# ARM_Motor.net
KiCad netlist of a schematic drawn in Altium Designer
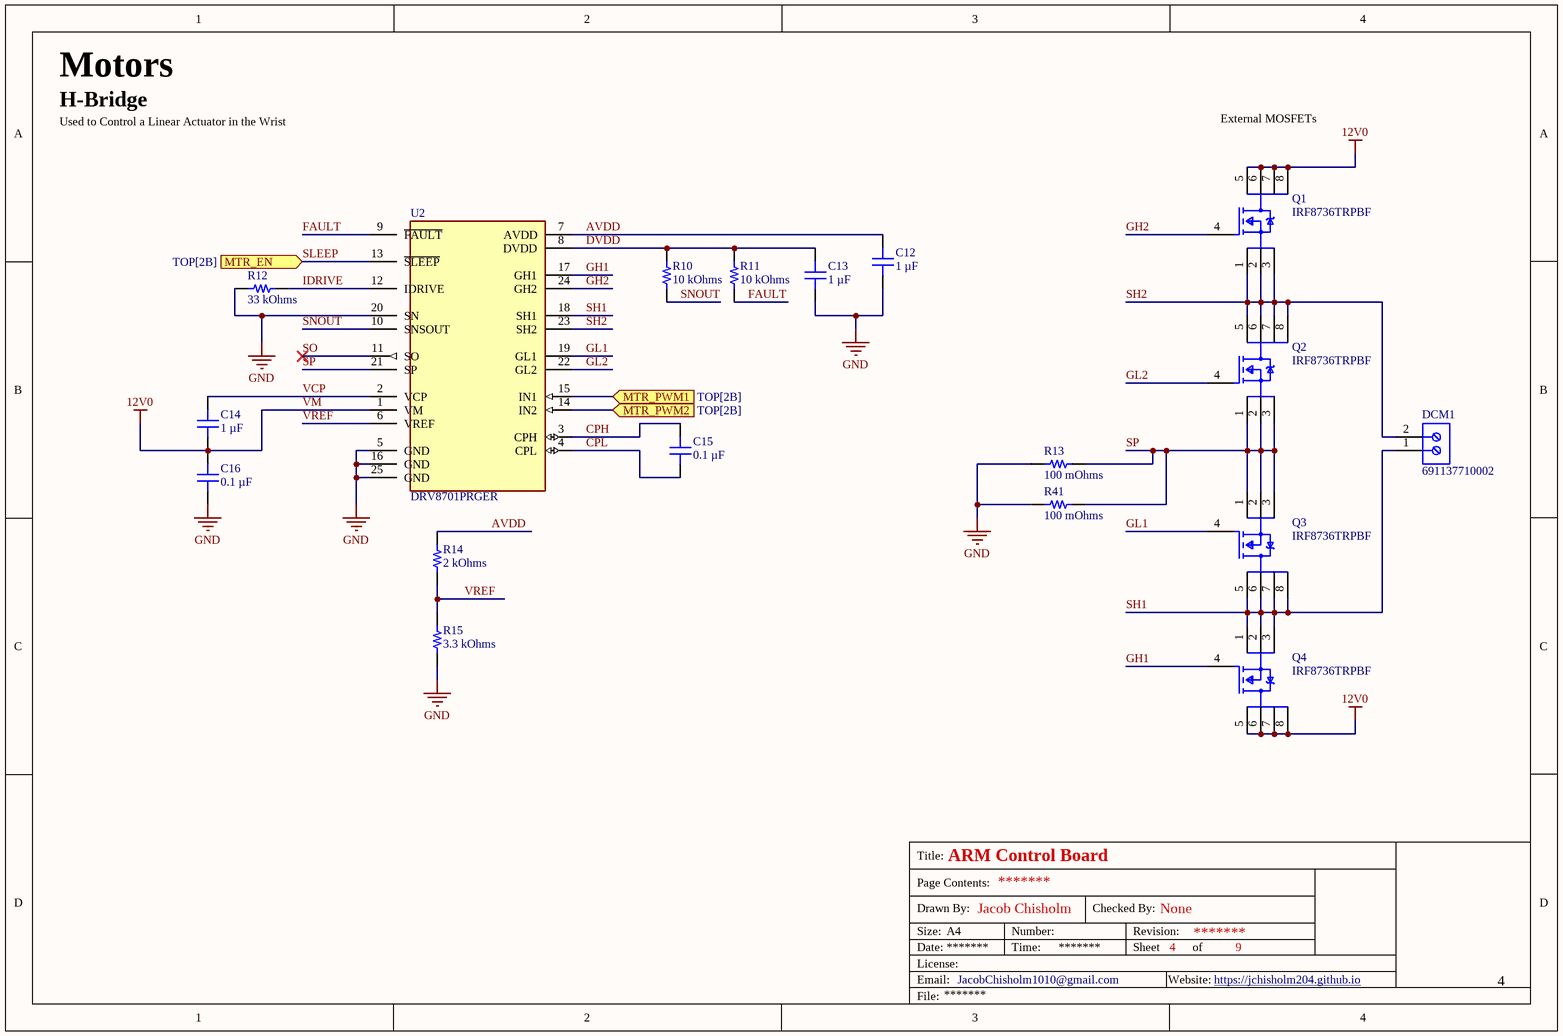
[diagram p0: ARM_Motor.SchDoc]

(export (version "E")
  (design (tool "Eeschema 10.0.6"))
  (components
    (comp (ref "C12")
      (value "1 µF")
      (footprint "CAP 0603_1608")
      (description "CAP0603 X7R 1UF 10% 50V")
      (fields
        (field (name "PART NUMBER") "GMC10X7R105K50NT")
        (field (name "MANUFACTURER") "Cal-Chip Electronics, Inc.")
      )
      (libsource (lib "Celestial Altium Library - altium_library") (part "Capacitor"))
    )
    (comp (ref "C13")
      (value "1 µF")
      (footprint "CAP 0603_1608")
      (description "CAP0603 X7R 1UF 10% 50V")
      (fields
        (field (name "PART NUMBER") "GMC10X7R105K50NT")
        (field (name "MANUFACTURER") "Cal-Chip Electronics, Inc.")
      )
      (libsource (lib "Celestial Altium Library - altium_library") (part "Capacitor"))
    )
    (comp (ref "C14")
      (value "1 µF")
      (footprint "CAP 0603_1608")
      (description "CAP0603 X7R 1UF 10% 50V")
      (fields
        (field (name "PART NUMBER") "GMC10X7R105K50NT")
        (field (name "MANUFACTURER") "Cal-Chip Electronics, Inc.")
      )
      (libsource (lib "Celestial Altium Library - altium_library") (part "Capacitor"))
    )
    (comp (ref "C15")
      (value "0.1 µF")
      (footprint "CAP 0603_1608")
      (description "CAP0603 X7R .1UF 10% 25V")
      (fields
        (field (name "PART NUMBER") "GMC10X7R104K25NT")
        (field (name "MANUFACTURER") "Cal-Chip Electronics, Inc.")
      )
      (libsource (lib "Celestial Altium Library - altium_library") (part "Capacitor"))
    )
    (comp (ref "C16")
      (value "0.1 µF")
      (footprint "CAP 0603_1608")
      (description "CAP0603 X7R .1UF 10% 25V")
      (fields
        (field (name "PART NUMBER") "GMC10X7R104K25NT")
        (field (name "MANUFACTURER") "Cal-Chip Electronics, Inc.")
      )
      (libsource (lib "Celestial Altium Library - altium_library") (part "Capacitor"))
    )
    (comp (ref "DCM1")
      (value "691137710002")
      (footprint "691137710002")
      (libsource (lib "Altium Content Vault") (part "TBL - 1R - 02P - Screw"))
    )
    (comp (ref "Q1")
      (value "IRF8736TRPBF")
      (footprint "FP-PG-DSO-8-MFG")
      (description "MOSFET N-CH 30V 18A 8-SOIC")
      (fields
        (field (name "MANUFACTURER") "Infineon")
        (field (name "OCTOPART") "https://octopart.com/irf8736trpbf-infineon-65873731")
      )
      (libsource (lib "Altium Content Vault") (part "6c4379695d6b9ddabb25581bf066c8b"))
    )
    (comp (ref "Q2")
      (value "IRF8736TRPBF")
      (footprint "FP-PG-DSO-8-MFG")
      (description "MOSFET N-CH 30V 18A 8-SOIC")
      (fields
        (field (name "MANUFACTURER") "Infineon")
        (field (name "OCTOPART") "https://octopart.com/irf8736trpbf-infineon-65873731")
      )
      (libsource (lib "Altium Content Vault") (part "6c4379695d6b9ddabb25581bf066c8b"))
    )
    (comp (ref "Q3")
      (value "IRF8736TRPBF")
      (footprint "FP-PG-DSO-8-MFG")
      (description "MOSFET N-CH 30V 18A 8-SOIC")
      (fields
        (field (name "MANUFACTURER") "Infineon")
        (field (name "OCTOPART") "https://octopart.com/irf8736trpbf-infineon-65873731")
      )
      (libsource (lib "Altium Content Vault") (part "6c4379695d6b9ddabb25581bf066c8b"))
    )
    (comp (ref "Q4")
      (value "IRF8736TRPBF")
      (footprint "FP-PG-DSO-8-MFG")
      (description "MOSFET N-CH 30V 18A 8-SOIC")
      (fields
        (field (name "MANUFACTURER") "Infineon")
        (field (name "OCTOPART") "https://octopart.com/irf8736trpbf-infineon-65873731")
      )
      (libsource (lib "Altium Content Vault") (part "6c4379695d6b9ddabb25581bf066c8b"))
    )
    (comp (ref "R10")
      (value "10 kOhms")
      (footprint "RES 0603_1608")
      (description "RES 10K OHM 0.01% 1/10W 0603")
      (fields
        (field (name "PART NUMBER") "RNCF0603TKW10K0")
        (field (name "MANUFACTURER") "Stackpole Electronics Inc")
      )
      (libsource (lib "Celestial Altium Library - altium_library") (part "Resistor"))
    )
    (comp (ref "R11")
      (value "10 kOhms")
      (footprint "RES 0603_1608")
      (description "RES 10K OHM 0.01% 1/10W 0603")
      (fields
        (field (name "PART NUMBER") "RNCF0603TKW10K0")
        (field (name "MANUFACTURER") "Stackpole Electronics Inc")
      )
      (libsource (lib "Celestial Altium Library - altium_library") (part "Resistor"))
    )
    (comp (ref "R12")
      (value "33 kOhms")
      (footprint "RES 0603_1608")
      (description "RES 33K OHM 0.5% 1/8W 0603")
      (fields
        (field (name "PART NUMBER") "ERJ-H3ED3302V")
        (field (name "MANUFACTURER") "Panasonic Electronic Components")
      )
      (libsource (lib "Celestial Altium Library - altium_library") (part "Resistor"))
    )
    (comp (ref "R13")
      (value "100 mOhms")
      (footprint "RES 2512_6432")
      (description "RES 0.1 OHM 1% 3W 2512")
      (fields (field (name "PART NUMBER") "CSR2512C0R1F") (field (name "MANUFACTURER") "Riedon"))
      (libsource (lib "Celestial Altium Library - altium_library") (part "Resistor"))
    )
    (comp (ref "R14")
      (value "2 kOhms")
      (footprint "RES 0603_1608")
      (description "PTN0603 10PPM 2K 0.1% S T1 E1")
      (fields
        (field (name "PART NUMBER") "PTN0603Y2001BST1")
        (field (name "MANUFACTURER") "Vishay Dale Thin Film")
      )
      (libsource (lib "Celestial Altium Library - altium_library") (part "Resistor"))
    )
    (comp (ref "R15")
      (value "3.3 kOhms")
      (footprint "RES 0603_1608")
      (description "RES 3.3K OHM 0.05% 1/8W 0603")
      (fields
        (field (name "PART NUMBER") "ERA-3VRW3301V")
        (field (name "MANUFACTURER") "Panasonic Electronic Components")
      )
      (libsource (lib "Celestial Altium Library - altium_library") (part "Resistor"))
    )
    (comp (ref "R41")
      (value "100 mOhms")
      (footprint "RES 2512_6432")
      (description "RES 0.1 OHM 1% 3W 2512")
      (fields (field (name "PART NUMBER") "CSR2512C0R1F") (field (name "MANUFACTURER") "Riedon"))
      (libsource (lib "Celestial Altium Library - altium_library") (part "Resistor"))
    )
    (comp (ref "U2")
      (value "DRV8701PRGER")
      (footprint "FP-RGE0024F-MFG")
      (description "IC MOTOR DRIVER 0V-5.5V 24VQFN")
      (libsource (lib "Altium Content Vault") (part "195a063a5fe8fd11522510fbc263874"))
    )
  )
  (nets
    (net (code "1") (name "/AVDD") (class "Default")
      (node (ref "C12") (pin "2") (pinfunction "2_2") (pintype "passive"))
      (node (ref "R14") (pin "2") (pinfunction "2_2") (pintype "passive"))
      (node (ref "U2") (pin "7") (pinfunction "AVDD_7") (pintype "power_in"))
    )
    (net (code "2") (name "/CPH") (class "Default")
      (node (ref "C15") (pin "2") (pinfunction "2_2") (pintype "passive"))
      (node (ref "U2") (pin "3") (pinfunction "CPH_3") (pintype "bidirectional"))
    )
    (net (code "3") (name "/CPL") (class "Default")
      (node (ref "C15") (pin "1") (pinfunction "1_1") (pintype "passive"))
      (node (ref "U2") (pin "4") (pinfunction "CPL_4") (pintype "bidirectional"))
    )
    (net (code "4") (name "/DVDD") (class "Default")
      (node (ref "C13") (pin "2") (pinfunction "2_2") (pintype "passive"))
      (node (ref "R10") (pin "2") (pinfunction "2_2") (pintype "passive"))
      (node (ref "R11") (pin "2") (pinfunction "2_2") (pintype "passive"))
      (node (ref "U2") (pin "8") (pinfunction "DVDD_8") (pintype "power_in"))
    )
    (net (code "5") (name "/FAULT") (class "Default")
      (node (ref "R11") (pin "1") (pinfunction "1_1") (pintype "passive"))
      (node (ref "U2") (pin "9") (pinfunction "~{FAULT}_9") (pintype "passive"))
    )
    (net (code "6") (name "/GH1") (class "Default")
      (node (ref "Q4") (pin "4") (pinfunction "G_4") (pintype "passive"))
      (node (ref "U2") (pin "17") (pinfunction "GH1_17") (pintype "passive"))
    )
    (net (code "7") (name "/GH2") (class "Default")
      (node (ref "Q1") (pin "4") (pinfunction "G_4") (pintype "passive"))
      (node (ref "U2") (pin "24") (pinfunction "GH2_24") (pintype "passive"))
    )
    (net (code "8") (name "/GL1") (class "Default")
      (node (ref "Q3") (pin "4") (pinfunction "G_4") (pintype "passive"))
      (node (ref "U2") (pin "19") (pinfunction "GL1_19") (pintype "passive"))
    )
    (net (code "9") (name "/GL2") (class "Default")
      (node (ref "Q2") (pin "4") (pinfunction "G_4") (pintype "passive"))
      (node (ref "U2") (pin "22") (pinfunction "GL2_22") (pintype "passive"))
    )
    (net (code "10") (name "/IDRIVE") (class "Default")
      (node (ref "R12") (pin "1") (pinfunction "1_1") (pintype "passive"))
      (node (ref "U2") (pin "12") (pinfunction "IDRIVE_12") (pintype "passive"))
    )
    (net (code "11") (name "/MTR_PWM1") (class "Default")
      (node (ref "U2") (pin "15") (pinfunction "IN1_15") (pintype "input"))
    )
    (net (code "12") (name "/MTR_PWM2") (class "Default")
      (node (ref "U2") (pin "14") (pinfunction "IN2_14") (pintype "input"))
    )
    (net (code "13") (name "/SH1") (class "Default")
      (node (ref "DCM1") (pin "1") (pinfunction "1_1") (pintype "passive"))
      (node (ref "Q3") (pin "5") (pinfunction "D_5") (pintype "passive"))
      (node (ref "Q3") (pin "6") (pinfunction "D_6") (pintype "passive"))
      (node (ref "Q3") (pin "7") (pinfunction "D_7") (pintype "passive"))
      (node (ref "Q3") (pin "8") (pinfunction "D_8") (pintype "passive"))
      (node (ref "Q4") (pin "1") (pinfunction "S_1") (pintype "passive"))
      (node (ref "Q4") (pin "2") (pinfunction "S_2") (pintype "passive"))
      (node (ref "Q4") (pin "3") (pinfunction "S_3") (pintype "passive"))
      (node (ref "U2") (pin "18") (pinfunction "SH1_18") (pintype "passive"))
    )
    (net (code "14") (name "/SH2") (class "Default")
      (node (ref "DCM1") (pin "2") (pinfunction "2_2") (pintype "passive"))
      (node (ref "Q1") (pin "1") (pinfunction "S_1") (pintype "passive"))
      (node (ref "Q1") (pin "2") (pinfunction "S_2") (pintype "passive"))
      (node (ref "Q1") (pin "3") (pinfunction "S_3") (pintype "passive"))
      (node (ref "Q2") (pin "5") (pinfunction "D_5") (pintype "passive"))
      (node (ref "Q2") (pin "6") (pinfunction "D_6") (pintype "passive"))
      (node (ref "Q2") (pin "7") (pinfunction "D_7") (pintype "passive"))
      (node (ref "Q2") (pin "8") (pinfunction "D_8") (pintype "passive"))
      (node (ref "U2") (pin "23") (pinfunction "SH2_23") (pintype "passive"))
    )
    (net (code "15") (name "/SLEEP") (class "Default")
      (node (ref "U2") (pin "13") (pinfunction "~{SLEEP}_13") (pintype "passive"))
    )
    (net (code "16") (name "/SNOUT") (class "Default")
      (node (ref "R10") (pin "1") (pinfunction "1_1") (pintype "passive"))
      (node (ref "U2") (pin "10") (pinfunction "SNSOUT_10") (pintype "passive"))
    )
    (net (code "17") (name "/SO") (class "Default")
      (node (ref "U2") (pin "11") (pinfunction "SO_11") (pintype "output+no_connect"))
    )
    (net (code "18") (name "/SP") (class "Default")
      (node (ref "Q2") (pin "1") (pinfunction "S_1") (pintype "passive"))
      (node (ref "Q2") (pin "2") (pinfunction "S_2") (pintype "passive"))
      (node (ref "Q2") (pin "3") (pinfunction "S_3") (pintype "passive"))
      (node (ref "Q3") (pin "1") (pinfunction "S_1") (pintype "passive"))
      (node (ref "Q3") (pin "2") (pinfunction "S_2") (pintype "passive"))
      (node (ref "Q3") (pin "3") (pinfunction "S_3") (pintype "passive"))
      (node (ref "R13") (pin "2") (pinfunction "2_2") (pintype "passive"))
      (node (ref "R41") (pin "2") (pinfunction "2_2") (pintype "passive"))
      (node (ref "U2") (pin "21") (pinfunction "SP_21") (pintype "passive"))
    )
    (net (code "19") (name "/VCP") (class "Default")
      (node (ref "C14") (pin "2") (pinfunction "2_2") (pintype "passive"))
      (node (ref "U2") (pin "2") (pinfunction "VCP_2") (pintype "passive"))
    )
    (net (code "20") (name "/VREF") (class "Default")
      (node (ref "R14") (pin "1") (pinfunction "1_1") (pintype "passive"))
      (node (ref "R15") (pin "2") (pinfunction "2_2") (pintype "passive"))
      (node (ref "U2") (pin "6") (pinfunction "VREF_6") (pintype "passive"))
    )
    (net (code "21") (name "12V0") (class "Default")
      (node (ref "C14") (pin "1") (pinfunction "1_1") (pintype "passive"))
      (node (ref "C16") (pin "2") (pinfunction "2_2") (pintype "passive"))
      (node (ref "Q1") (pin "5") (pinfunction "D_5") (pintype "passive"))
      (node (ref "Q1") (pin "6") (pinfunction "D_6") (pintype "passive"))
      (node (ref "Q1") (pin "7") (pinfunction "D_7") (pintype "passive"))
      (node (ref "Q1") (pin "8") (pinfunction "D_8") (pintype "passive"))
      (node (ref "Q4") (pin "5") (pinfunction "D_5") (pintype "passive"))
      (node (ref "Q4") (pin "6") (pinfunction "D_6") (pintype "passive"))
      (node (ref "Q4") (pin "7") (pinfunction "D_7") (pintype "passive"))
      (node (ref "Q4") (pin "8") (pinfunction "D_8") (pintype "passive"))
      (node (ref "U2") (pin "1") (pinfunction "VM_1") (pintype "passive"))
    )
    (net (code "22") (name "GND") (class "Default")
      (node (ref "C12") (pin "1") (pinfunction "1_1") (pintype "passive"))
      (node (ref "C13") (pin "1") (pinfunction "1_1") (pintype "passive"))
      (node (ref "C16") (pin "1") (pinfunction "1_1") (pintype "passive"))
      (node (ref "R12") (pin "2") (pinfunction "2_2") (pintype "passive"))
      (node (ref "R13") (pin "1") (pinfunction "1_1") (pintype "passive"))
      (node (ref "R15") (pin "1") (pinfunction "1_1") (pintype "passive"))
      (node (ref "R41") (pin "1") (pinfunction "1_1") (pintype "passive"))
      (node (ref "U2") (pin "16") (pinfunction "GND_16") (pintype "power_in"))
      (node (ref "U2") (pin "20") (pinfunction "SN_20") (pintype "passive"))
      (node (ref "U2") (pin "25") (pinfunction "GND_25") (pintype "power_in"))
      (node (ref "U2") (pin "5") (pinfunction "GND_5") (pintype "power_in"))
    )
  )
)
